# external.net
KiCad netlist of a schematic drawn in Altium Designer
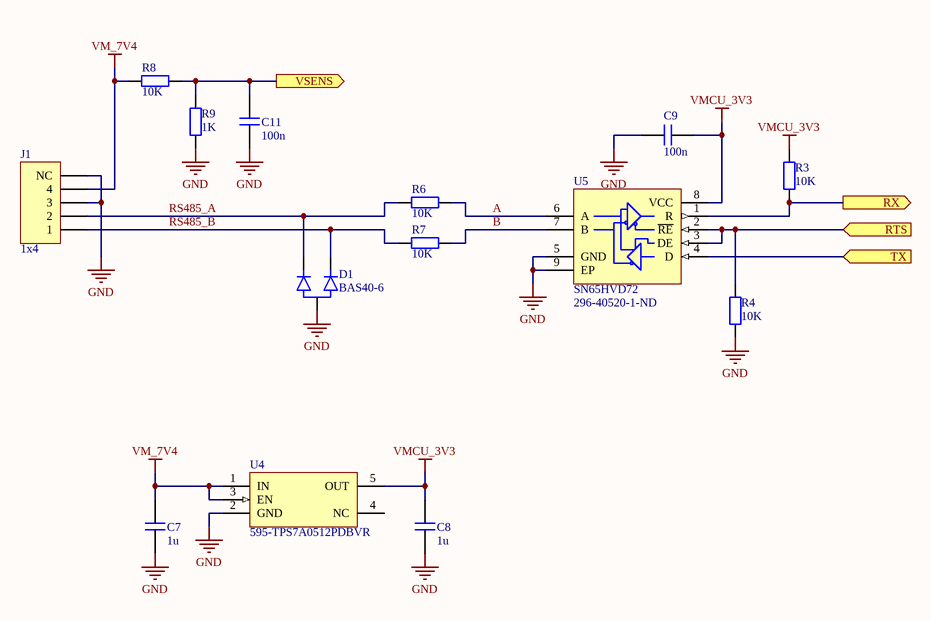
[diagram p0: external.SchDoc]

(export (version "E")
  (design (tool "Eeschema 10.0.6"))
  (components
    (comp (ref "C7")
      (value "1u")
      (footprint "CAPC2012X11N")
      (description "Capacitor")
      (fields (field (name "Comment") "cap"))
      (libsource (lib "lib_passives") (part "cap"))
    )
    (comp (ref "C8")
      (value "1u")
      (footprint "CAPC2012X11N")
      (description "Capacitor")
      (fields (field (name "Comment") "cap"))
      (libsource (lib "lib_passives") (part "cap"))
    )
    (comp (ref "C9")
      (value "100n")
      (footprint "CAPC1005X06N")
      (description "Capacitor")
      (fields (field (name "Comment") "cap"))
      (libsource (lib "lib_passives") (part "cap"))
    )
    (comp (ref "C11")
      (value "100n")
      (footprint "CAPC1005X06N")
      (description "Capacitor")
      (fields (field (name "Comment") "cap"))
      (libsource (lib "lib_passives") (part "cap"))
    )
    (comp (ref "D1")
      (value "BAS40-6")
      (footprint "SOT23_CA")
      (description "Diode Common Anode")
      (libsource (lib "lib_actives") (part "diode_dual_ca"))
    )
    (comp (ref "J1")
      (value "1x4")
      (footprint "sm04b-pass")
      (description "2.0mm pitch/Wire-to-board (Crimp style/IDC) / Wire-to-wire (Crimp style/IDC)")
      (libsource (lib "lib_jst") (part "sm04b-pass"))
    )
    (comp (ref "R3")
      (value "10K")
      (footprint "RESC1005X04N")
      (description "Resistor")
      (fields (field (name "Comment") "res"))
      (libsource (lib "lib_passives") (part "res"))
    )
    (comp (ref "R4")
      (value "10K")
      (footprint "RESC1005X04N")
      (description "Resistor")
      (fields (field (name "Comment") "res"))
      (libsource (lib "lib_passives") (part "res"))
    )
    (comp (ref "R6")
      (value "10K")
      (footprint "RESC1005X04N")
      (description "Resistor")
      (fields (field (name "Comment") "res"))
      (libsource (lib "lib_passives") (part "res"))
    )
    (comp (ref "R7")
      (value "10K")
      (footprint "RESC1005X04N")
      (description "Resistor")
      (fields (field (name "Comment") "res"))
      (libsource (lib "lib_passives") (part "res"))
    )
    (comp (ref "R8")
      (value "10K")
      (footprint "RESC1005X04N")
      (description "Resistor")
      (fields (field (name "Comment") "res"))
      (libsource (lib "") (part "res_1"))
    )
    (comp (ref "R9")
      (value "1K")
      (footprint "RESC1005X04N")
      (description "Resistor")
      (fields (field (name "Comment") "res"))
      (libsource (lib "lib_passives") (part "res"))
    )
    (comp (ref "U4")
      (value "595-TPS7A0512PDBVR")
      (footprint "SOT95P280X145-5N")
      (description "TPS7A05 1-µA Ultralow IQ, 200-mA, Low-Dropout Regulator")
      (libsource (lib "lib_ti") (part "tps7a0512pdbvr"))
    )
    (comp (ref "U5")
      (value "SN65HVD72")
      (footprint "SON65P300X100_HS-9N")
      (description "3.3-V Supply RS-485 With IEC ESD Protection")
      (fields (field (name "SUPPLIER PART NUMBER 1") "296-40520-1-ND"))
      (libsource (lib "lib_ti") (part "sn65hvd72"))
    )
  )
  (nets
    (net (code "1") (name "/A") (class "Default")
      (node (ref "R6") (pin "2") (pinfunction "2_2") (pintype "passive"))
      (node (ref "U5") (pin "6") (pinfunction "A_6") (pintype "passive"))
    )
    (net (code "2") (name "/B") (class "Default")
      (node (ref "R7") (pin "2") (pinfunction "2_2") (pintype "passive"))
      (node (ref "U5") (pin "7") (pinfunction "B_7") (pintype "passive"))
    )
    (net (code "3") (name "/RS485_A") (class "Default")
      (node (ref "D1") (pin "C2") (pinfunction "C2_C2") (pintype "passive"))
      (node (ref "J1") (pin "2") (pinfunction "2_2") (pintype "passive"))
      (node (ref "R6") (pin "1") (pinfunction "1_1") (pintype "passive"))
    )
    (net (code "4") (name "/RS485_B") (class "Default")
      (node (ref "D1") (pin "C1") (pinfunction "C1_C1") (pintype "passive"))
      (node (ref "J1") (pin "1") (pinfunction "1_1") (pintype "passive"))
      (node (ref "R7") (pin "1") (pinfunction "1_1") (pintype "passive"))
    )
    (net (code "5") (name "/RTS") (class "Default")
      (node (ref "R4") (pin "2") (pinfunction "2_2") (pintype "passive"))
      (node (ref "U5") (pin "2") (pinfunction "RE_2") (pintype "input"))
      (node (ref "U5") (pin "3") (pinfunction "DE_3") (pintype "input"))
    )
    (net (code "6") (name "/RX") (class "Default")
      (node (ref "R3") (pin "1") (pinfunction "1_1") (pintype "passive"))
      (node (ref "U5") (pin "1") (pinfunction "R_1") (pintype "output"))
    )
    (net (code "7") (name "/TX") (class "Default")
      (node (ref "U5") (pin "4") (pinfunction "D_4") (pintype "input"))
    )
    (net (code "8") (name "/VSENS") (class "Default")
      (node (ref "C11") (pin "2") (pinfunction "2_2") (pintype "passive"))
      (node (ref "R8") (pin "1") (pinfunction "1_1") (pintype "passive"))
      (node (ref "R9") (pin "2") (pinfunction "2_2") (pintype "passive"))
    )
    (net (code "9") (name "GND") (class "Default")
      (node (ref "C11") (pin "1") (pinfunction "1_1") (pintype "passive"))
      (node (ref "C7") (pin "1") (pinfunction "1_1") (pintype "passive"))
      (node (ref "C8") (pin "1") (pinfunction "1_1") (pintype "passive"))
      (node (ref "C9") (pin "2") (pinfunction "2_2") (pintype "passive"))
      (node (ref "D1") (pin "A") (pinfunction "A_A") (pintype "passive"))
      (node (ref "J1") (pin "3") (pinfunction "3_3") (pintype "passive"))
      (node (ref "J1") (pin "ANCHOR") (pinfunction "NC_ANCHOR") (pintype "passive"))
      (node (ref "R4") (pin "1") (pinfunction "1_1") (pintype "passive"))
      (node (ref "R9") (pin "1") (pinfunction "1_1") (pintype "passive"))
      (node (ref "U4") (pin "2") (pinfunction "GND_2") (pintype "power_in"))
      (node (ref "U5") (pin "5") (pinfunction "GND_5") (pintype "power_in"))
      (node (ref "U5") (pin "9") (pinfunction "EP_9") (pintype "power_in"))
    )
    (net (code "10") (name "VMCU_3V3") (class "Default")
      (node (ref "C8") (pin "2") (pinfunction "2_2") (pintype "passive"))
      (node (ref "C9") (pin "1") (pinfunction "1_1") (pintype "passive"))
      (node (ref "R3") (pin "2") (pinfunction "2_2") (pintype "passive"))
      (node (ref "U4") (pin "5") (pinfunction "OUT_5") (pintype "power_in"))
      (node (ref "U5") (pin "8") (pinfunction "VCC_8") (pintype "power_in"))
    )
    (net (code "11") (name "VM_7V4") (class "Default")
      (node (ref "C7") (pin "2") (pinfunction "2_2") (pintype "passive"))
      (node (ref "J1") (pin "4") (pinfunction "4_4") (pintype "passive"))
      (node (ref "R8") (pin "2") (pinfunction "2_2") (pintype "passive"))
      (node (ref "U4") (pin "1") (pinfunction "IN_1") (pintype "power_in"))
      (node (ref "U4") (pin "3") (pinfunction "EN_3") (pintype "input"))
    )
    (net (code "12") (name "unconnected-(U4-NC-Pad4)") (class "Default")
      (node (ref "U4") (pin "4") (pinfunction "NC_4") (pintype "passive"))
    )
  )
)
